# placa_adquisicion_ecg.net
KiCad netlist of a schematic drawn in Altium Designer
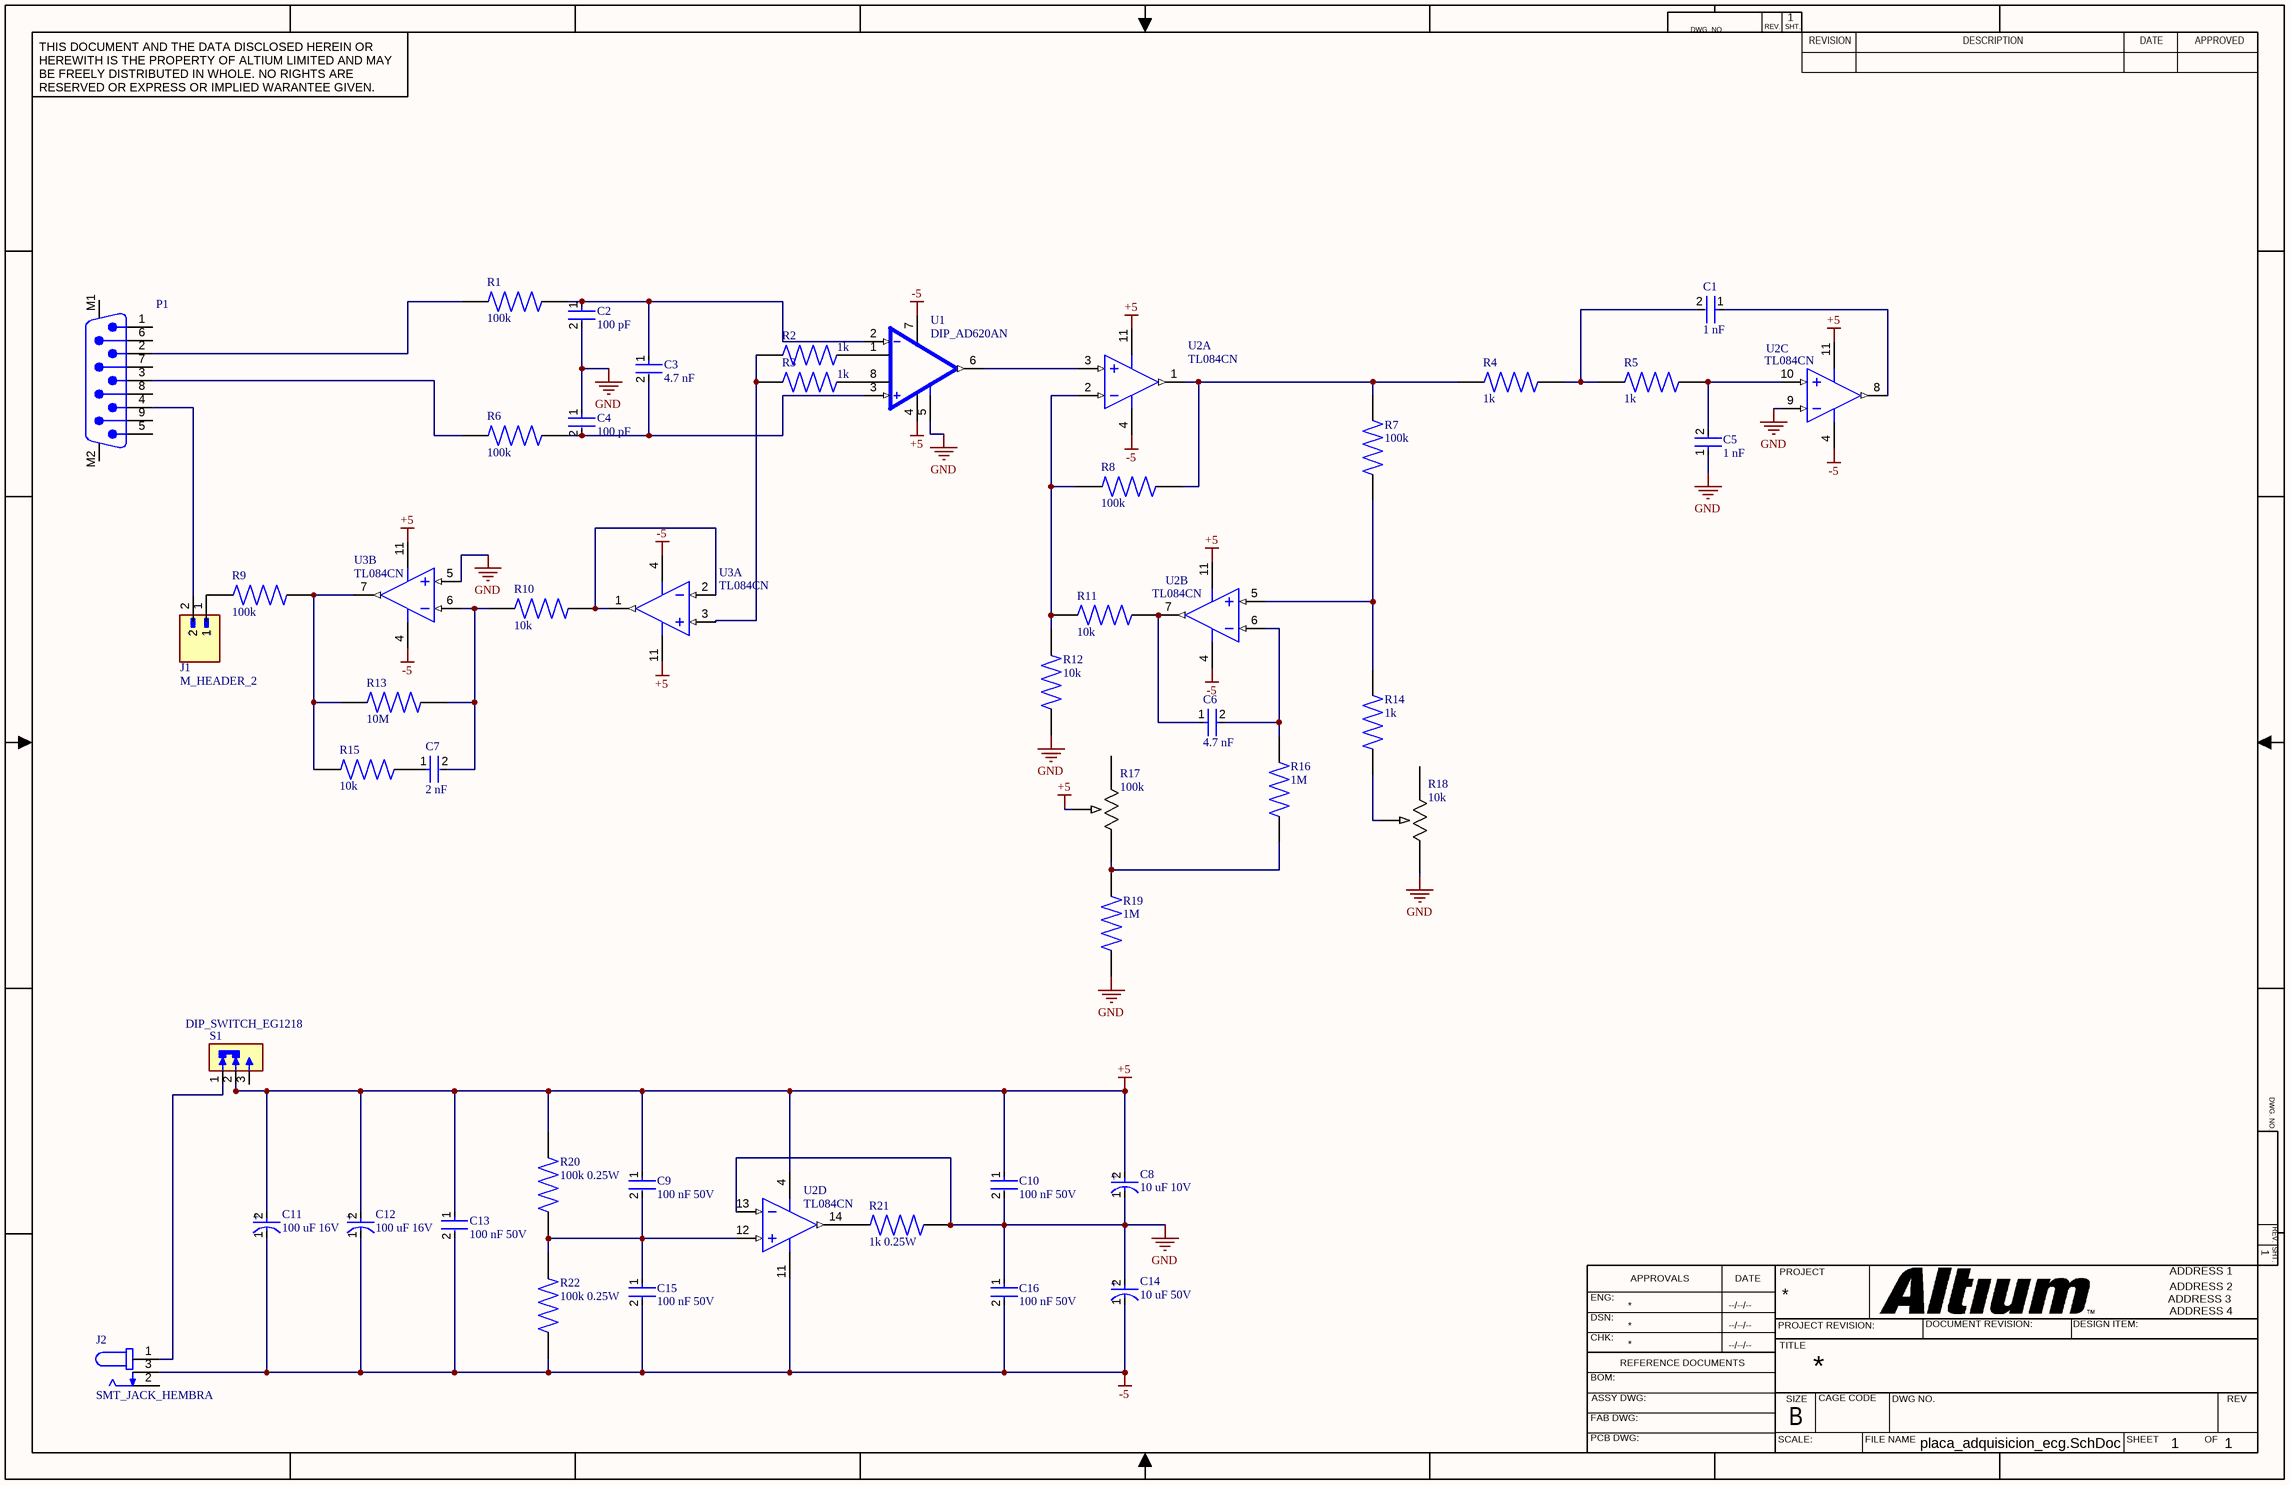
[diagram p0: placa_adquisicion_ecg.SchDoc]

(export (version "E")
  (design (tool "Eeschema 10.0.6"))
  (components
    (comp (ref "C1")
      (value "1 nF")
      (footprint "C_1206_50V")
      (description "Multilayer Ceramic Capacitor, C Series, 100 Pf, - 5%, C0g / Np0, 50 V, 1206 [3216 Metric]")
      (fields
        (field (name "OCTOPART") "https://octopart.com/c1206c101j5gactu-kemet-102340")
        (field (name "MANUFACTURER PART NUMBER") "C1206C101J5GACTU")
      )
      (libsource (lib "placa_adquisicion_ecg") (part "C_1206_50V"))
    )
    (comp (ref "C2")
      (value "100 pF")
      (footprint "C_1206_50V")
      (description "Multilayer Ceramic Capacitor, C Series, 100 Pf, - 5%, C0g / Np0, 50 V, 1206 [3216 Metric]")
      (fields
        (field (name "OCTOPART") "https://octopart.com/c1206c101j5gactu-kemet-102340")
        (field (name "MANUFACTURER PART NUMBER") "C1206C101J5GACTU")
      )
      (libsource (lib "placa_adquisicion_ecg") (part "C_1206_50V"))
    )
    (comp (ref "C3")
      (value "4.7 nF")
      (footprint "C_1206_50V")
      (description "Multilayer Ceramic Capacitor, C Series, 100 Pf, - 5%, C0g / Np0, 50 V, 1206 [3216 Metric]")
      (fields
        (field (name "OCTOPART") "https://octopart.com/c1206c101j5gactu-kemet-102340")
        (field (name "MANUFACTURER PART NUMBER") "C1206C101J5GACTU")
      )
      (libsource (lib "placa_adquisicion_ecg") (part "C_1206_50V"))
    )
    (comp (ref "C4")
      (value "100 pF")
      (footprint "C_1206_50V")
      (description "Multilayer Ceramic Capacitor, C Series, 100 Pf, - 5%, C0g / Np0, 50 V, 1206 [3216 Metric]")
      (fields
        (field (name "OCTOPART") "https://octopart.com/c1206c101j5gactu-kemet-102340")
        (field (name "MANUFACTURER PART NUMBER") "C1206C101J5GACTU")
      )
      (libsource (lib "placa_adquisicion_ecg") (part "C_1206_50V"))
    )
    (comp (ref "C5")
      (value "1 nF")
      (footprint "C_1206_50V")
      (description "Multilayer Ceramic Capacitor, C Series, 100 Pf, - 5%, C0g / Np0, 50 V, 1206 [3216 Metric]")
      (fields
        (field (name "OCTOPART") "https://octopart.com/c1206c101j5gactu-kemet-102340")
        (field (name "MANUFACTURER PART NUMBER") "C1206C101J5GACTU")
      )
      (libsource (lib "placa_adquisicion_ecg") (part "C_1206_50V"))
    )
    (comp (ref "C6")
      (value "4.7 nF")
      (footprint "C_1206_50V")
      (description "Multilayer Ceramic Capacitor, C Series, 100 Pf, - 5%, C0g / Np0, 50 V, 1206 [3216 Metric]")
      (fields
        (field (name "OCTOPART") "https://octopart.com/c1206c101j5gactu-kemet-102340")
        (field (name "MANUFACTURER PART NUMBER") "C1206C101J5GACTU")
      )
      (libsource (lib "placa_adquisicion_ecg") (part "C_1206_50V"))
    )
    (comp (ref "C7")
      (value "2 nF")
      (footprint "C_1206_50V")
      (description "Multilayer Ceramic Capacitor, C Series, 100 Pf, - 5%, C0g / Np0, 50 V, 1206 [3216 Metric]")
      (fields
        (field (name "OCTOPART") "https://octopart.com/c1206c101j5gactu-kemet-102340")
        (field (name "MANUFACTURER PART NUMBER") "C1206C101J5GACTU")
      )
      (libsource (lib "placa_adquisicion_ecg") (part "C_1206_50V"))
    )
    (comp (ref "C8")
      (value "10 uF 10V")
      (footprint "C_DIP_100uF_16V")
      (description "Aluminum Electrolytic Capacitors (Radial Lead Type) AEC-Q200 Qualified 100uF ±20% 16V")
      (fields (field (name "TOLERANCE") "20%") (field (name "VOLTAGE") "16V"))
      (libsource (lib "placa_adquisicion_ecg") (part "C_DIP_100uF_16V"))
    )
    (comp (ref "C9")
      (value "100 nF 50V")
      (footprint "C_1206_50V")
      (description "Multilayer Ceramic Capacitor, C Series, 100 Pf, - 5%, C0g / Np0, 50 V, 1206 [3216 Metric]")
      (fields
        (field (name "OCTOPART") "https://octopart.com/c1206c101j5gactu-kemet-102340")
        (field (name "MANUFACTURER PART NUMBER") "C1206C101J5GACTU")
      )
      (libsource (lib "placa_adquisicion_ecg") (part "C_1206_50V"))
    )
    (comp (ref "C10")
      (value "100 nF 50V")
      (footprint "C_1206_50V")
      (description "Multilayer Ceramic Capacitor, C Series, 100 Pf, - 5%, C0g / Np0, 50 V, 1206 [3216 Metric]")
      (fields
        (field (name "OCTOPART") "https://octopart.com/c1206c101j5gactu-kemet-102340")
        (field (name "MANUFACTURER PART NUMBER") "C1206C101J5GACTU")
      )
      (libsource (lib "placa_adquisicion_ecg") (part "C_1206_50V"))
    )
    (comp (ref "C11")
      (value "100 uF 16V")
      (footprint "C_DIP_100uF_16V")
      (description "Aluminum Electrolytic Capacitors (Radial Lead Type) AEC-Q200 Qualified 100uF ±20% 16V")
      (fields (field (name "TOLERANCE") "20%") (field (name "VOLTAGE") "16V"))
      (libsource (lib "placa_adquisicion_ecg") (part "C_DIP_100uF_16V"))
    )
    (comp (ref "C12")
      (value "100 uF 16V")
      (footprint "C_DIP_100uF_16V")
      (description "Aluminum Electrolytic Capacitors (Radial Lead Type) AEC-Q200 Qualified 100uF ±20% 16V")
      (fields (field (name "TOLERANCE") "20%") (field (name "VOLTAGE") "16V"))
      (libsource (lib "placa_adquisicion_ecg") (part "C_DIP_100uF_16V"))
    )
    (comp (ref "C13")
      (value "100 nF 50V")
      (footprint "C_1206_50V")
      (description "Multilayer Ceramic Capacitor, C Series, 100 Pf, - 5%, C0g / Np0, 50 V, 1206 [3216 Metric]")
      (fields
        (field (name "OCTOPART") "https://octopart.com/c1206c101j5gactu-kemet-102340")
        (field (name "MANUFACTURER PART NUMBER") "C1206C101J5GACTU")
      )
      (libsource (lib "placa_adquisicion_ecg") (part "C_1206_50V"))
    )
    (comp (ref "C14")
      (value "10 uF 50V")
      (footprint "C_DIP_100uF_16V")
      (description "Aluminum Electrolytic Capacitors (Radial Lead Type) AEC-Q200 Qualified 100uF ±20% 16V")
      (fields (field (name "TOLERANCE") "20%") (field (name "VOLTAGE") "16V"))
      (libsource (lib "placa_adquisicion_ecg") (part "C_DIP_100uF_16V"))
    )
    (comp (ref "C15")
      (value "100 nF 50V")
      (footprint "C_1206_50V")
      (description "Multilayer Ceramic Capacitor, C Series, 100 Pf, - 5%, C0g / Np0, 50 V, 1206 [3216 Metric]")
      (fields
        (field (name "OCTOPART") "https://octopart.com/c1206c101j5gactu-kemet-102340")
        (field (name "MANUFACTURER PART NUMBER") "C1206C101J5GACTU")
      )
      (libsource (lib "placa_adquisicion_ecg") (part "C_1206_50V"))
    )
    (comp (ref "C16")
      (value "100 nF 50V")
      (footprint "C_1206_50V")
      (description "Multilayer Ceramic Capacitor, C Series, 100 Pf, - 5%, C0g / Np0, 50 V, 1206 [3216 Metric]")
      (fields
        (field (name "OCTOPART") "https://octopart.com/c1206c101j5gactu-kemet-102340")
        (field (name "MANUFACTURER PART NUMBER") "C1206C101J5GACTU")
      )
      (libsource (lib "placa_adquisicion_ecg") (part "C_1206_50V"))
    )
    (comp (ref "J1")
      (value "M_HEADER_2")
      (footprint "M_HEADER_2")
      (description "2.54mm (0.1) Pitch SIL Vertical Throughboard Pin Header, 6.1mm mating pin height, tin, 2 contacts")
      (fields (field (name "MF") "Harwin") (field (name "MP") "M20-9990246"))
      (libsource (lib "placa_adquisicion_ecg") (part "M_HEADER_2"))
    )
    (comp (ref "J2")
      (value "SMT_JACK_HEMBRA")
      (footprint "SMT_JACK_HEMBRA")
      (description "2.0 x 6.3 mm, 5.0 A, Horizontal, Surface Mount (SMT), Dc Power Jack Connector")
      (fields (field (name "MF") "Same Sky") (field (name "MP") "PJ-036AH-SMT-TR"))
      (libsource (lib "placa_adquisicion_ecg") (part "SMT_JACK_HEMBRA"))
    )
    (comp (ref "P1")
      (value "618009231221")
      (footprint "DIP_DB9M_90DEG")
      (libsource (lib "placa_adquisicion_ecg") (part "DIP_DB9M_90DEG"))
    )
    (comp (ref "R1")
      (value "100k")
      (footprint "R_1206_0.25W")
      (description "10 kOhms Â±1% 0.25W, 1/4W Chip Resistor 1206 (3216 Metric) Moisture Resistant Thick Film")
      (fields (field (name "MF") "Yageo") (field (name "MP") "RC1206FR-0710KL"))
      (libsource (lib "placa_adquisicion_ecg") (part "R_1206_0.25W"))
    )
    (comp (ref "R2")
      (value "1k")
      (footprint "R_1206_0.25W")
      (description "10 kOhms Â±1% 0.25W, 1/4W Chip Resistor 1206 (3216 Metric) Moisture Resistant Thick Film")
      (fields (field (name "MF") "Yageo") (field (name "MP") "RC1206FR-0710KL"))
      (libsource (lib "placa_adquisicion_ecg") (part "R_1206_0.25W"))
    )
    (comp (ref "R3")
      (value "1k")
      (footprint "R_1206_0.25W")
      (description "10 kOhms Â±1% 0.25W, 1/4W Chip Resistor 1206 (3216 Metric) Moisture Resistant Thick Film")
      (fields (field (name "MF") "Yageo") (field (name "MP") "RC1206FR-0710KL"))
      (libsource (lib "placa_adquisicion_ecg") (part "R_1206_0.25W"))
    )
    (comp (ref "R4")
      (value "1k")
      (footprint "R_1206_0.25W")
      (description "10 kOhms Â±1% 0.25W, 1/4W Chip Resistor 1206 (3216 Metric) Moisture Resistant Thick Film")
      (fields (field (name "MF") "Yageo") (field (name "MP") "RC1206FR-0710KL"))
      (libsource (lib "placa_adquisicion_ecg") (part "R_1206_0.25W"))
    )
    (comp (ref "R5")
      (value "1k")
      (footprint "R_1206_0.25W")
      (description "10 kOhms Â±1% 0.25W, 1/4W Chip Resistor 1206 (3216 Metric) Moisture Resistant Thick Film")
      (fields (field (name "MF") "Yageo") (field (name "MP") "RC1206FR-0710KL"))
      (libsource (lib "placa_adquisicion_ecg") (part "R_1206_0.25W"))
    )
    (comp (ref "R6")
      (value "100k")
      (footprint "R_1206_0.25W")
      (description "10 kOhms Â±1% 0.25W, 1/4W Chip Resistor 1206 (3216 Metric) Moisture Resistant Thick Film")
      (fields (field (name "MF") "Yageo") (field (name "MP") "RC1206FR-0710KL"))
      (libsource (lib "placa_adquisicion_ecg") (part "R_1206_0.25W"))
    )
    (comp (ref "R7")
      (value "100k")
      (footprint "R_1206_0.25W")
      (description "10 kOhms Â±1% 0.25W, 1/4W Chip Resistor 1206 (3216 Metric) Moisture Resistant Thick Film")
      (fields (field (name "MF") "Yageo") (field (name "MP") "RC1206FR-0710KL"))
      (libsource (lib "placa_adquisicion_ecg") (part "R_1206_0.25W"))
    )
    (comp (ref "R8")
      (value "100k")
      (footprint "R_1206_0.25W")
      (description "10 kOhms Â±1% 0.25W, 1/4W Chip Resistor 1206 (3216 Metric) Moisture Resistant Thick Film")
      (fields (field (name "MF") "Yageo") (field (name "MP") "RC1206FR-0710KL"))
      (libsource (lib "placa_adquisicion_ecg") (part "R_1206_0.25W"))
    )
    (comp (ref "R9")
      (value "100k")
      (footprint "R_1206_0.25W")
      (description "10 kOhms Â±1% 0.25W, 1/4W Chip Resistor 1206 (3216 Metric) Moisture Resistant Thick Film")
      (fields (field (name "MF") "Yageo") (field (name "MP") "RC1206FR-0710KL"))
      (libsource (lib "placa_adquisicion_ecg") (part "R_1206_0.25W"))
    )
    (comp (ref "R10")
      (value "10k")
      (footprint "R_1206_0.25W")
      (description "10 kOhms Â±1% 0.25W, 1/4W Chip Resistor 1206 (3216 Metric) Moisture Resistant Thick Film")
      (fields (field (name "MF") "Yageo") (field (name "MP") "RC1206FR-0710KL"))
      (libsource (lib "placa_adquisicion_ecg") (part "R_1206_0.25W"))
    )
    (comp (ref "R11")
      (value "10k")
      (footprint "R_1206_0.25W")
      (description "10 kOhms Â±1% 0.25W, 1/4W Chip Resistor 1206 (3216 Metric) Moisture Resistant Thick Film")
      (fields (field (name "MF") "Yageo") (field (name "MP") "RC1206FR-0710KL"))
      (libsource (lib "placa_adquisicion_ecg") (part "R_1206_0.25W"))
    )
    (comp (ref "R12")
      (value "10k")
      (footprint "R_1206_0.25W")
      (description "10 kOhms Â±1% 0.25W, 1/4W Chip Resistor 1206 (3216 Metric) Moisture Resistant Thick Film")
      (fields (field (name "MF") "Yageo") (field (name "MP") "RC1206FR-0710KL"))
      (libsource (lib "placa_adquisicion_ecg") (part "R_1206_0.25W"))
    )
    (comp (ref "R13")
      (value "10M")
      (footprint "R_1206_0.25W")
      (description "10 kOhms Â±1% 0.25W, 1/4W Chip Resistor 1206 (3216 Metric) Moisture Resistant Thick Film")
      (fields (field (name "MF") "Yageo") (field (name "MP") "RC1206FR-0710KL"))
      (libsource (lib "placa_adquisicion_ecg") (part "R_1206_0.25W"))
    )
    (comp (ref "R14")
      (value "1k")
      (footprint "R_1206_0.25W")
      (description "10 kOhms Â±1% 0.25W, 1/4W Chip Resistor 1206 (3216 Metric) Moisture Resistant Thick Film")
      (fields (field (name "MF") "Yageo") (field (name "MP") "RC1206FR-0710KL"))
      (libsource (lib "placa_adquisicion_ecg") (part "R_1206_0.25W"))
    )
    (comp (ref "R15")
      (value "10k")
      (footprint "R_1206_0.25W")
      (description "10 kOhms Â±1% 0.25W, 1/4W Chip Resistor 1206 (3216 Metric) Moisture Resistant Thick Film")
      (fields (field (name "MF") "Yageo") (field (name "MP") "RC1206FR-0710KL"))
      (libsource (lib "placa_adquisicion_ecg") (part "R_1206_0.25W"))
    )
    (comp (ref "R16")
      (value "1M")
      (footprint "R_1206_0.25W")
      (description "10 kOhms Â±1% 0.25W, 1/4W Chip Resistor 1206 (3216 Metric) Moisture Resistant Thick Film")
      (fields (field (name "MF") "Yageo") (field (name "MP") "RC1206FR-0710KL"))
      (libsource (lib "placa_adquisicion_ecg") (part "R_1206_0.25W"))
    )
    (comp (ref "R17")
      (value "100k")
      (footprint "POT_TRIMMER")
      (description "Description")
      (fields
        (field (name "MANUFACTURER_PART_NUMBER") "PV36W104C01B00")
        (field (name "COPYRIGHT") "Copyright (C) 2025 Ultra Librarian. All rights reserved.")
      )
      (libsource (lib "placa_adquisicion_ecg") (part "POT_TRIMMER"))
    )
    (comp (ref "R18")
      (value "10k")
      (footprint "POT_TRIMMER")
      (description "Description")
      (fields
        (field (name "MANUFACTURER_PART_NUMBER") "PV36W104C01B00")
        (field (name "COPYRIGHT") "Copyright (C) 2025 Ultra Librarian. All rights reserved.")
      )
      (libsource (lib "placa_adquisicion_ecg") (part "POT_TRIMMER"))
    )
    (comp (ref "R19")
      (value "1M")
      (footprint "R_1206_0.25W")
      (description "10 kOhms Â±1% 0.25W, 1/4W Chip Resistor 1206 (3216 Metric) Moisture Resistant Thick Film")
      (fields (field (name "MF") "Yageo") (field (name "MP") "RC1206FR-0710KL"))
      (libsource (lib "placa_adquisicion_ecg") (part "R_1206_0.25W"))
    )
    (comp (ref "R20")
      (value "100k 0.25W")
      (footprint "R_1206_0.25W")
      (description "10 kOhms Â±1% 0.25W, 1/4W Chip Resistor 1206 (3216 Metric) Moisture Resistant Thick Film")
      (fields (field (name "MF") "Yageo") (field (name "MP") "RC1206FR-0710KL"))
      (libsource (lib "placa_adquisicion_ecg") (part "R_1206_0.25W"))
    )
    (comp (ref "R21")
      (value "1k 0.25W")
      (footprint "R_1206_0.25W")
      (description "10 kOhms Â±1% 0.25W, 1/4W Chip Resistor 1206 (3216 Metric) Moisture Resistant Thick Film")
      (fields (field (name "MF") "Yageo") (field (name "MP") "RC1206FR-0710KL"))
      (libsource (lib "placa_adquisicion_ecg") (part "R_1206_0.25W"))
    )
    (comp (ref "R22")
      (value "100k 0.25W")
      (footprint "R_1206_0.25W")
      (description "10 kOhms Â±1% 0.25W, 1/4W Chip Resistor 1206 (3216 Metric) Moisture Resistant Thick Film")
      (fields (field (name "MF") "Yageo") (field (name "MP") "RC1206FR-0710KL"))
      (libsource (lib "placa_adquisicion_ecg") (part "R_1206_0.25W"))
    )
    (comp (ref "S1")
      (value "DIP_SWITCH_EG1218")
      (footprint "DIP_SWITCH_EG128")
      (description "Slide Switch, EG Series, SPDT, Non-Shorting, ON-ON, 200mA DC, 30VDC, PC Pin ¦ E-Switch EG1218")
      (fields (field (name "MF") "E-Switch") (field (name "MP") "EG1218"))
      (libsource (lib "placa_adquisicion_ecg") (part "DIP_SWITCH_EG128"))
    )
    (comp (ref "U1")
      (value "DIP_AD620AN")
      (footprint "DIP_AD620AN")
      (description "Instrumentation Amplifier 1 Circuit - 8-PDIP")
      (fields (field (name "MF") "Analog Devices") (field (name "MP") "AD620AN"))
      (libsource (lib "placa_adquisicion_ecg") (part "DIP_AD620AN"))
    )
    (comp (ref "U2")
      (value "TL084CN")
      (footprint "DIP_TL084CN")
      (description "JFET-Input Operational Amplifier, 7 to 36 V, 0 to 70 degC, 14-pin DIP (N14), Pb-Free (RoHS)")
      (fields (field (name "MANUFACTURER") "Texas Instruments"))
      (libsource (lib "placa_adquisicion_ecg") (part "DIP_TL084CN"))
    )
    (comp (ref "U3")
      (value "TL084CN")
      (footprint "DIP_TL084CN")
      (description "JFET-Input Operational Amplifier, 7 to 36 V, 0 to 70 degC, 14-pin DIP (N14), Pb-Free (RoHS)")
      (fields (field (name "MANUFACTURER") "Texas Instruments"))
      (libsource (lib "placa_adquisicion_ecg") (part "DIP_TL084CN"))
    )
  )
  (nets
    (net (code "1") (name "+5") (class "Default")
      (node (ref "C10") (pin "1") (pinfunction "1_1") (pintype "passive"))
      (node (ref "C11") (pin "2") (pinfunction "A_2") (pintype "passive"))
      (node (ref "C12") (pin "2") (pinfunction "A_2") (pintype "passive"))
      (node (ref "C13") (pin "1") (pinfunction "1_1") (pintype "passive"))
      (node (ref "C8") (pin "2") (pinfunction "A_2") (pintype "passive"))
      (node (ref "C9") (pin "1") (pinfunction "1_1") (pintype "passive"))
      (node (ref "R17") (pin "2") (pinfunction "2_2") (pintype "passive"))
      (node (ref "R20") (pin "2") (pinfunction "2_2") (pintype "passive"))
      (node (ref "S1") (pin "2") (pinfunction "COM_2") (pintype "passive"))
      (node (ref "U1") (pin "4") (pinfunction "-VS_4") (pintype "power_in"))
      (node (ref "U2") (pin "11") (pinfunction "VCC-_11") (pintype "power_in"))
      (node (ref "U2") (pin "4") (pinfunction "VCC+_4") (pintype "power_in"))
      (node (ref "U3") (pin "11") (pinfunction "VCC-_11") (pintype "power_in"))
    )
    (net (code "2") (name "-5") (class "Default")
      (node (ref "C11") (pin "1") (pinfunction "C_1") (pintype "passive"))
      (node (ref "C12") (pin "1") (pinfunction "C_1") (pintype "passive"))
      (node (ref "C13") (pin "2") (pinfunction "2_2") (pintype "passive"))
      (node (ref "C14") (pin "1") (pinfunction "C_1") (pintype "passive"))
      (node (ref "C15") (pin "2") (pinfunction "2_2") (pintype "passive"))
      (node (ref "C16") (pin "2") (pinfunction "2_2") (pintype "passive"))
      (node (ref "J2") (pin "3") (pinfunction "3_3") (pintype "passive"))
      (node (ref "R22") (pin "1") (pinfunction "1_1") (pintype "passive"))
      (node (ref "U1") (pin "7") (pinfunction "+VS_7") (pintype "power_in"))
      (node (ref "U2") (pin "11") (pinfunction "VCC-_11") (pintype "power_in"))
      (node (ref "U2") (pin "4") (pinfunction "VCC+_4") (pintype "power_in"))
      (node (ref "U3") (pin "4") (pinfunction "VCC+_4") (pintype "power_in"))
    )
    (net (code "3") (name "GND") (class "Default")
      (node (ref "C10") (pin "2") (pinfunction "2_2") (pintype "passive"))
      (node (ref "C14") (pin "2") (pinfunction "A_2") (pintype "passive"))
      (node (ref "C16") (pin "1") (pinfunction "1_1") (pintype "passive"))
      (node (ref "C2") (pin "2") (pinfunction "2_2") (pintype "passive"))
      (node (ref "C4") (pin "1") (pinfunction "1_1") (pintype "passive"))
      (node (ref "C5") (pin "1") (pinfunction "1_1") (pintype "passive"))
      (node (ref "C8") (pin "1") (pinfunction "C_1") (pintype "passive"))
      (node (ref "R12") (pin "1") (pinfunction "1_1") (pintype "passive"))
      (node (ref "R18") (pin "1") (pinfunction "1_1") (pintype "passive"))
      (node (ref "R19") (pin "1") (pinfunction "1_1") (pintype "passive"))
      (node (ref "R21") (pin "2") (pinfunction "2_2") (pintype "passive"))
      (node (ref "U1") (pin "5") (pinfunction "REF_5") (pintype "power_in"))
      (node (ref "U2") (pin "13") (pinfunction "IN4-_13") (pintype "input"))
      (node (ref "U2") (pin "9") (pinfunction "IN3-_9") (pintype "input"))
      (node (ref "U3") (pin "5") (pinfunction "IN2+_5") (pintype "input"))
    )
    (net (code "4") (name "Net-(C1-Pad2)") (class "Default")
      (node (ref "C1") (pin "2") (pinfunction "2_2") (pintype "passive"))
      (node (ref "R4") (pin "2") (pinfunction "2_2") (pintype "passive"))
      (node (ref "R5") (pin "1") (pinfunction "1_1") (pintype "passive"))
    )
    (net (code "5") (name "Net-(C7-Pad1)") (class "Default")
      (node (ref "C7") (pin "1") (pinfunction "1_1") (pintype "passive"))
      (node (ref "R15") (pin "2") (pinfunction "2_2") (pintype "passive"))
    )
    (net (code "6") (name "Net-(J1-Pad1)") (class "Default")
      (node (ref "J1") (pin "1") (pinfunction "1_1") (pintype "passive"))
      (node (ref "R9") (pin "1") (pinfunction "1_1") (pintype "passive"))
    )
    (net (code "7") (name "Net-(J1-Pad2)") (class "Default")
      (node (ref "J1") (pin "2") (pinfunction "2_2") (pintype "passive"))
      (node (ref "P1") (pin "4") (pinfunction "4_4") (pintype "passive"))
    )
    (net (code "8") (name "Net-(P1-Pad2)") (class "Default")
      (node (ref "P1") (pin "2") (pinfunction "2_2") (pintype "passive"))
      (node (ref "R1") (pin "1") (pinfunction "1_1") (pintype "passive"))
    )
    (net (code "9") (name "Net-(P1-Pad3)") (class "Default")
      (node (ref "P1") (pin "3") (pinfunction "3_3") (pintype "passive"))
      (node (ref "R6") (pin "1") (pinfunction "1_1") (pintype "passive"))
    )
    (net (code "10") (name "Net-(R14-Pad1)") (class "Default")
      (node (ref "R14") (pin "1") (pinfunction "1_1") (pintype "passive"))
      (node (ref "R18") (pin "2") (pinfunction "2_2") (pintype "passive"))
    )
    (net (code "11") (name "Net-(R16-Pad1)") (class "Default")
      (node (ref "R16") (pin "1") (pinfunction "1_1") (pintype "passive"))
      (node (ref "R17") (pin "1") (pinfunction "1_1") (pintype "passive"))
      (node (ref "R19") (pin "2") (pinfunction "2_2") (pintype "passive"))
    )
    (net (code "12") (name "Net-(S1-NC)") (class "Default")
      (node (ref "J2") (pin "1") (pinfunction "1_1") (pintype "passive"))
      (node (ref "S1") (pin "1") (pinfunction "NC_1") (pintype "passive"))
    )
    (net (code "13") (name "Net-(U1-+IN)") (class "Default")
      (node (ref "C3") (pin "2") (pinfunction "2_2") (pintype "passive"))
      (node (ref "C4") (pin "2") (pinfunction "2_2") (pintype "passive"))
      (node (ref "R6") (pin "2") (pinfunction "2_2") (pintype "passive"))
      (node (ref "U1") (pin "3") (pinfunction "+IN_3") (pintype "input"))
    )
    (net (code "14") (name "Net-(U1--IN)") (class "Default")
      (node (ref "C2") (pin "1") (pinfunction "1_1") (pintype "passive"))
      (node (ref "C3") (pin "1") (pinfunction "1_1") (pintype "passive"))
      (node (ref "R1") (pin "2") (pinfunction "2_2") (pintype "passive"))
      (node (ref "U1") (pin "2") (pinfunction "-IN_2") (pintype "input"))
    )
    (net (code "15") (name "Net-(U1-OUTPUT)") (class "Default")
      (node (ref "U1") (pin "6") (pinfunction "OUTPUT_6") (pintype "output"))
      (node (ref "U2") (pin "3") (pinfunction "IN1+_3") (pintype "input"))
    )
    (net (code "16") (name "Net-(U1-RG_1)") (class "Default")
      (node (ref "R2") (pin "2") (pinfunction "2_2") (pintype "passive"))
      (node (ref "U1") (pin "1") (pinfunction "RG_1_1") (pintype "passive"))
    )
    (net (code "17") (name "Net-(U1-RG_8)") (class "Default")
      (node (ref "R3") (pin "2") (pinfunction "2_2") (pintype "passive"))
      (node (ref "U1") (pin "8") (pinfunction "RG_8_8") (pintype "passive"))
    )
    (net (code "18") (name "Net-(U2A-IN1-)") (class "Default")
      (node (ref "R11") (pin "1") (pinfunction "1_1") (pintype "passive"))
      (node (ref "R12") (pin "2") (pinfunction "2_2") (pintype "passive"))
      (node (ref "R8") (pin "1") (pinfunction "1_1") (pintype "passive"))
      (node (ref "U2") (pin "2") (pinfunction "IN1-_2") (pintype "input"))
    )
    (net (code "19") (name "Net-(U2A-OUT1)") (class "Default")
      (node (ref "R4") (pin "1") (pinfunction "1_1") (pintype "passive"))
      (node (ref "R7") (pin "2") (pinfunction "2_2") (pintype "passive"))
      (node (ref "R8") (pin "2") (pinfunction "2_2") (pintype "passive"))
      (node (ref "U2") (pin "1") (pinfunction "OUT1_1") (pintype "output"))
    )
    (net (code "20") (name "Net-(U2B-IN2+)") (class "Default")
      (node (ref "R14") (pin "2") (pinfunction "2_2") (pintype "passive"))
      (node (ref "R7") (pin "1") (pinfunction "1_1") (pintype "passive"))
      (node (ref "U2") (pin "5") (pinfunction "IN2+_5") (pintype "input"))
    )
    (net (code "21") (name "Net-(U2B-IN2-)") (class "Default")
      (node (ref "C6") (pin "2") (pinfunction "2_2") (pintype "passive"))
      (node (ref "R16") (pin "2") (pinfunction "2_2") (pintype "passive"))
      (node (ref "U2") (pin "6") (pinfunction "IN2-_6") (pintype "input"))
    )
    (net (code "22") (name "Net-(U2B-OUT2)") (class "Default")
      (node (ref "C6") (pin "1") (pinfunction "1_1") (pintype "passive"))
      (node (ref "R11") (pin "2") (pinfunction "2_2") (pintype "passive"))
      (node (ref "U2") (pin "7") (pinfunction "OUT2_7") (pintype "output"))
    )
    (net (code "23") (name "Net-(U2C-IN3+)") (class "Default")
      (node (ref "C5") (pin "2") (pinfunction "2_2") (pintype "passive"))
      (node (ref "R5") (pin "2") (pinfunction "2_2") (pintype "passive"))
      (node (ref "U2") (pin "10") (pinfunction "IN3+_10") (pintype "input"))
    )
    (net (code "24") (name "Net-(U2C-OUT3)") (class "Default")
      (node (ref "C1") (pin "1") (pinfunction "1_1") (pintype "passive"))
      (node (ref "U2") (pin "8") (pinfunction "OUT3_8") (pintype "output"))
    )
    (net (code "25") (name "Net-(U2D-IN4+)") (class "Default")
      (node (ref "C15") (pin "1") (pinfunction "1_1") (pintype "passive"))
      (node (ref "C9") (pin "2") (pinfunction "2_2") (pintype "passive"))
      (node (ref "R20") (pin "1") (pinfunction "1_1") (pintype "passive"))
      (node (ref "R22") (pin "2") (pinfunction "2_2") (pintype "passive"))
      (node (ref "U2") (pin "12") (pinfunction "IN4+_12") (pintype "input"))
    )
    (net (code "26") (name "Net-(U2D-OUT4)") (class "Default")
      (node (ref "R21") (pin "1") (pinfunction "1_1") (pintype "passive"))
      (node (ref "U2") (pin "14") (pinfunction "OUT4_14") (pintype "output"))
    )
    (net (code "27") (name "Net-(U3A-IN1+)") (class "Default")
      (node (ref "R2") (pin "1") (pinfunction "1_1") (pintype "passive"))
      (node (ref "R3") (pin "1") (pinfunction "1_1") (pintype "passive"))
      (node (ref "U3") (pin "3") (pinfunction "IN1+_3") (pintype "input"))
    )
    (net (code "28") (name "Net-(U3A-IN1-)") (class "Default")
      (node (ref "R10") (pin "2") (pinfunction "2_2") (pintype "passive"))
      (node (ref "U3") (pin "1") (pinfunction "OUT1_1") (pintype "output"))
      (node (ref "U3") (pin "2") (pinfunction "IN1-_2") (pintype "input"))
    )
    (net (code "29") (name "Net-(U3B-IN2-)") (class "Default")
      (node (ref "C7") (pin "2") (pinfunction "2_2") (pintype "passive"))
      (node (ref "R10") (pin "1") (pinfunction "1_1") (pintype "passive"))
      (node (ref "R13") (pin "2") (pinfunction "2_2") (pintype "passive"))
      (node (ref "U3") (pin "6") (pinfunction "IN2-_6") (pintype "input"))
    )
    (net (code "30") (name "Net-(U3B-OUT2)") (class "Default")
      (node (ref "R13") (pin "1") (pinfunction "1_1") (pintype "passive"))
      (node (ref "R15") (pin "1") (pinfunction "1_1") (pintype "passive"))
      (node (ref "R9") (pin "2") (pinfunction "2_2") (pintype "passive"))
      (node (ref "U3") (pin "7") (pinfunction "OUT2_7") (pintype "output"))
    )
    (net (code "31") (name "unconnected-(J2-Pad2)") (class "Default")
      (node (ref "J2") (pin "2") (pinfunction "2_2") (pintype "passive"))
    )
    (net (code "32") (name "unconnected-(P1-Pad1)") (class "Default")
      (node (ref "P1") (pin "1") (pinfunction "1_1") (pintype "passive"))
    )
    (net (code "33") (name "unconnected-(P1-Pad5)") (class "Default")
      (node (ref "P1") (pin "5") (pinfunction "5_5") (pintype "passive"))
    )
    (net (code "34") (name "unconnected-(P1-Pad6)") (class "Default")
      (node (ref "P1") (pin "6") (pinfunction "6_6") (pintype "passive"))
    )
    (net (code "35") (name "unconnected-(P1-Pad7)") (class "Default")
      (node (ref "P1") (pin "7") (pinfunction "7_7") (pintype "passive"))
    )
    (net (code "36") (name "unconnected-(P1-Pad8)") (class "Default")
      (node (ref "P1") (pin "8") (pinfunction "8_8") (pintype "passive"))
    )
    (net (code "37") (name "unconnected-(P1-Pad9)") (class "Default")
      (node (ref "P1") (pin "9") (pinfunction "9_9") (pintype "passive"))
    )
    (net (code "38") (name "unconnected-(P1-PadM1)") (class "Default")
      (node (ref "P1") (pin "M1") (pinfunction "M1_M1") (pintype "passive"))
    )
    (net (code "39") (name "unconnected-(P1-PadM2)") (class "Default")
      (node (ref "P1") (pin "M2") (pinfunction "M2_M2") (pintype "passive"))
    )
    (net (code "40") (name "unconnected-(R17-Pad3)") (class "Default")
      (node (ref "R17") (pin "3") (pinfunction "3_3") (pintype "passive"))
    )
    (net (code "41") (name "unconnected-(R18-Pad3)") (class "Default")
      (node (ref "R18") (pin "3") (pinfunction "3_3") (pintype "passive"))
    )
    (net (code "42") (name "unconnected-(S1-NO-Pad3)") (class "Default")
      (node (ref "S1") (pin "3") (pinfunction "NO_3") (pintype "passive"))
    )
  )
)
